# Sheet1.net
KiCad netlist of a schematic drawn in Altium Designer
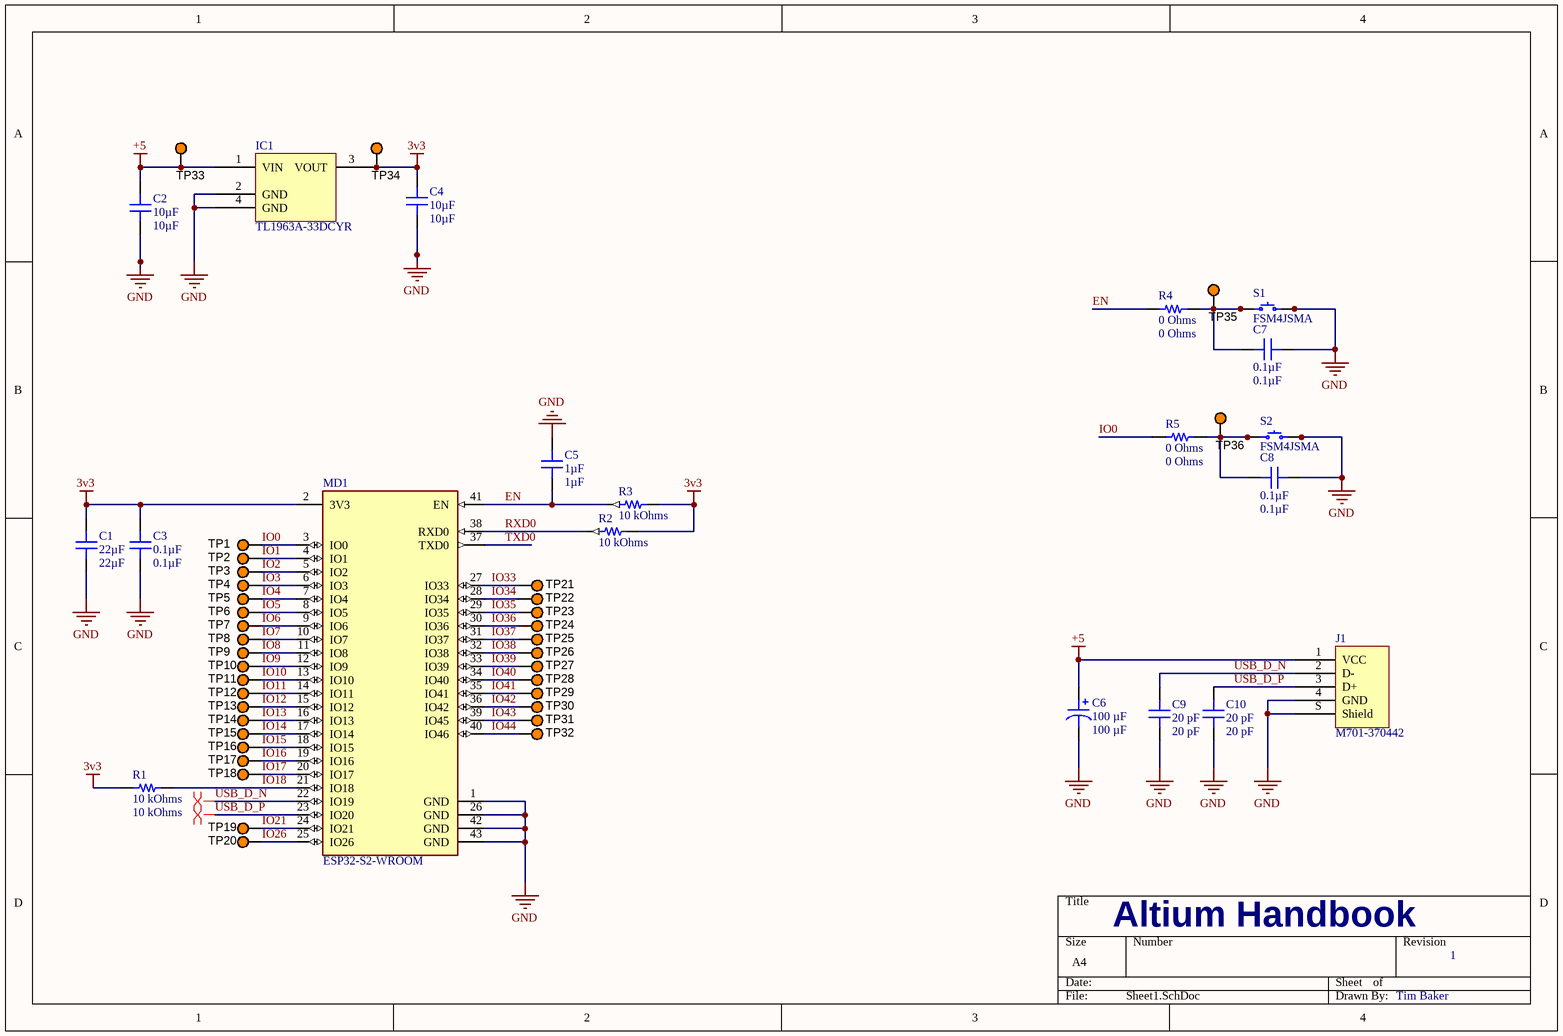
[diagram p0: Sheet1.SchDoc]

(export (version "E")
  (design (tool "Eeschema 10.0.6"))
  (components
    (comp (ref "C1")
      (value "22µF")
      (footprint "CAP 0805_2012")
      (description "CAP CER 22UF 10V X5R 0805")
      (fields (field (name "PART NUMBER") "0805ZD226MAT2A") (field (name "ALTIUM_VALUE") "22µF"))
      (libsource (lib "Celestial Altium Library - altium_library") (part "Capacitor"))
    )
    (comp (ref "C2")
      (value "10µF")
      (footprint "CAP 0805_2012")
      (description "CAP CER 10UF 10V X5R 0805")
      (fields (field (name "PART NUMBER") "0805ZD106KAT4A") (field (name "ALTIUM_VALUE") "10µF"))
      (libsource (lib "Celestial Altium Library - altium_library") (part "Capacitor"))
    )
    (comp (ref "C3")
      (value "0.1µF")
      (footprint "CAP 0805_2012")
      (description "CAP CER 0.1UF 10V X5R 0805")
      (fields (field (name "PART NUMBER") "0805ZD104KAT2A") (field (name "ALTIUM_VALUE") "0.1µF"))
      (libsource (lib "Celestial Altium Library - altium_library") (part "Capacitor"))
    )
    (comp (ref "C4")
      (value "10µF")
      (footprint "CAP 0805_2012")
      (description "CAP CER 10UF 10V X5R 0805")
      (fields (field (name "PART NUMBER") "0805ZD106KAT4A") (field (name "ALTIUM_VALUE") "10µF"))
      (libsource (lib "Celestial Altium Library - altium_library") (part "Capacitor"))
    )
    (comp (ref "C5")
      (value "1µF")
      (footprint "CAP 0805_2012")
      (description "CAP CER 1UF 10V X5R 0805")
      (fields (field (name "PART NUMBER") "0805ZD105KAT2A") (field (name "ALTIUM_VALUE") "1µF"))
      (libsource (lib "Celestial Altium Library - altium_library") (part "Capacitor"))
    )
    (comp (ref "C6")
      (value "100 µF")
      (footprint "CAP POL 2917_7343")
      (description "CAP TANT 100UF 10% 20V 2917")
      (fields (field (name "PART NUMBER") "T491X107K020AT") (field (name "ALTIUM_VALUE") "100 µF"))
      (libsource (lib "Celestial Altium Library - altium_library") (part "Polarised Capacitor"))
    )
    (comp (ref "C7")
      (value "0.1µF")
      (footprint "CAP 0805_2012")
      (description "CAP CER 0.1UF 10V X5R 0805")
      (fields (field (name "PART NUMBER") "0805ZD104KAT2A") (field (name "ALTIUM_VALUE") "0.1µF"))
      (libsource (lib "Celestial Altium Library - altium_library") (part "Capacitor"))
    )
    (comp (ref "C8")
      (value "0.1µF")
      (footprint "CAP 0805_2012")
      (description "CAP CER 0.1UF 10V X5R 0805")
      (fields (field (name "PART NUMBER") "0805ZD104KAT2A") (field (name "ALTIUM_VALUE") "0.1µF"))
      (libsource (lib "Celestial Altium Library - altium_library") (part "Capacitor"))
    )
    (comp (ref "C9")
      (value "20 pF")
      (footprint "CAP 0805_2012")
      (description "CAP CER 20PF 10V X8R 0805")
      (fields (field (name "PART NUMBER") "C0805C200G8HAC7800") (field (name "ALTIUM_VALUE") "20 pF"))
      (libsource (lib "Celestial Altium Library - altium_library") (part "Capacitor"))
    )
    (comp (ref "C10")
      (value "20 pF")
      (footprint "CAP 0805_2012")
      (description "CAP CER 20PF 10V X8R 0805")
      (fields (field (name "PART NUMBER") "C0805C200G8HAC7800") (field (name "ALTIUM_VALUE") "20 pF"))
      (libsource (lib "Celestial Altium Library - altium_library") (part "Capacitor"))
    )
    (comp (ref "IC1")
      (value "TL1963A-33DCYR")
      (footprint "TI SOT-223 DCY")
      (description "IC REG LINEAR 3.3V 1.5A SOT223-4")
      (libsource (lib "Celestial Altium Library - altium_library") (part "TI TL1963A DCY"))
    )
    (comp (ref "J1")
      (value "M701-370442")
      (footprint "HARWIN USB M701-370442")
      (description "CONN RCPT USB2.0 TYPEB 4P SMD RA")
      (libsource (lib "Celestial Altium Library - altium_library") (part "USB 2.0 Type B"))
    )
    (comp (ref "MD1")
      (value "ESP32-S2-WROOM")
      (footprint "FP-ESP32-S2-WROOM-MFG")
      (description "RX TXRX MOD WIFI SURFACE MOUNT")
      (libsource (lib "Altium Content Vault") (part "dfe856f8f0070eb901285bddcc8df6c"))
    )
    (comp (ref "R1")
      (value "10 kOhms")
      (footprint "RES 0805_2012")
      (description "RES 10K OHM 10% 1/8W 0805")
      (fields (field (name "PART NUMBER") "SG732ATTD103K") (field (name "ALTIUM_VALUE") "10 kOhms"))
      (libsource (lib "Celestial Altium Library - altium_library") (part "Resistor"))
    )
    (comp (ref "R2")
      (value "10 kOhms")
      (footprint "RES 0805_2012")
      (description "RES 10K OHM 10% 1/8W 0805")
      (fields (field (name "PART NUMBER") "SG732ATTD103K"))
      (libsource (lib "Celestial Altium Library - altium_library") (part "Resistor"))
    )
    (comp (ref "R3")
      (value "10 kOhms")
      (footprint "RES 0805_2012")
      (description "RES 10K OHM 10% 1/8W 0805")
      (fields (field (name "PART NUMBER") "SG732ATTD103K"))
      (libsource (lib "Celestial Altium Library - altium_library") (part "Resistor"))
    )
    (comp (ref "R4")
      (value "0 Ohms")
      (footprint "RES 0805_2012")
      (description "RES 0 OHM JUMPER 1/8W 0805")
      (fields (field (name "PART NUMBER") "CRCW08050000Z0EBC") (field (name "ALTIUM_VALUE") "0 Ohms"))
      (libsource (lib "") (part "Resistor_1"))
    )
    (comp (ref "R5")
      (value "0 Ohms")
      (footprint "RES 0805_2012")
      (description "RES 0 OHM JUMPER 1/8W 0805")
      (fields (field (name "PART NUMBER") "CRCW08050000Z0EBC") (field (name "ALTIUM_VALUE") "0 Ohms"))
      (libsource (lib "") (part "Resistor_1"))
    )
    (comp (ref "S1")
      (value "FSM4JSMA")
      (footprint "TE FSM4JSMA")
      (description "SWITCH TACTILE SPST-NO 0.05A 24V")
      (libsource (lib "Celestial Altium Library - altium_library") (part "SPST-NO 4 PIN"))
    )
    (comp (ref "S2")
      (value "FSM4JSMA")
      (footprint "TE FSM4JSMA")
      (description "SWITCH TACTILE SPST-NO 0.05A 24V")
      (libsource (lib "Celestial Altium Library - altium_library") (part "SPST-NO 4 PIN"))
    )
    (comp (ref "TP1")
      (value "Test Point Square")
      (footprint "New footprint 1")
      (description "1.5mm Square testpoint")
      (libsource (lib "Cuvos Pty Ltd") (part "TESTPOINT_ORANGE"))
    )
    (comp (ref "TP2")
      (value "Test Point Square")
      (footprint "New footprint 1")
      (description "1.5mm Square testpoint")
      (libsource (lib "Cuvos Pty Ltd") (part "TESTPOINT_ORANGE"))
    )
    (comp (ref "TP3")
      (value "Test Point Square")
      (footprint "New footprint 1")
      (description "1.5mm Square testpoint")
      (libsource (lib "Cuvos Pty Ltd") (part "TESTPOINT_ORANGE"))
    )
    (comp (ref "TP4")
      (value "Test Point Square")
      (footprint "New footprint 1")
      (description "1.5mm Square testpoint")
      (libsource (lib "Cuvos Pty Ltd") (part "TESTPOINT_ORANGE"))
    )
    (comp (ref "TP5")
      (value "Test Point Square")
      (footprint "New footprint 1")
      (description "1.5mm Square testpoint")
      (libsource (lib "Cuvos Pty Ltd") (part "TESTPOINT_ORANGE"))
    )
    (comp (ref "TP6")
      (value "Test Point Square")
      (footprint "New footprint 1")
      (description "1.5mm Square testpoint")
      (libsource (lib "Cuvos Pty Ltd") (part "TESTPOINT_ORANGE"))
    )
    (comp (ref "TP7")
      (value "Test Point Square")
      (footprint "New footprint 1")
      (description "1.5mm Square testpoint")
      (libsource (lib "Cuvos Pty Ltd") (part "TESTPOINT_ORANGE"))
    )
    (comp (ref "TP8")
      (value "Test Point Square")
      (footprint "New footprint 1")
      (description "1.5mm Square testpoint")
      (libsource (lib "Cuvos Pty Ltd") (part "TESTPOINT_ORANGE"))
    )
    (comp (ref "TP9")
      (value "Test Point Square")
      (footprint "New footprint 1")
      (description "1.5mm Square testpoint")
      (libsource (lib "Cuvos Pty Ltd") (part "TESTPOINT_ORANGE"))
    )
    (comp (ref "TP10")
      (value "Test Point Square")
      (footprint "New footprint 1")
      (description "1.5mm Square testpoint")
      (libsource (lib "Cuvos Pty Ltd") (part "TESTPOINT_ORANGE"))
    )
    (comp (ref "TP11")
      (value "Test Point Square")
      (footprint "New footprint 1")
      (description "1.5mm Square testpoint")
      (libsource (lib "Cuvos Pty Ltd") (part "TESTPOINT_ORANGE"))
    )
    (comp (ref "TP12")
      (value "Test Point Square")
      (footprint "New footprint 1")
      (description "1.5mm Square testpoint")
      (libsource (lib "Cuvos Pty Ltd") (part "TESTPOINT_ORANGE"))
    )
    (comp (ref "TP13")
      (value "Test Point Square")
      (footprint "New footprint 1")
      (description "1.5mm Square testpoint")
      (libsource (lib "Cuvos Pty Ltd") (part "TESTPOINT_ORANGE"))
    )
    (comp (ref "TP14")
      (value "Test Point Square")
      (footprint "New footprint 1")
      (description "1.5mm Square testpoint")
      (libsource (lib "Cuvos Pty Ltd") (part "TESTPOINT_ORANGE"))
    )
    (comp (ref "TP15")
      (value "Test Point Square")
      (footprint "New footprint 1")
      (description "1.5mm Square testpoint")
      (libsource (lib "Cuvos Pty Ltd") (part "TESTPOINT_ORANGE"))
    )
    (comp (ref "TP16")
      (value "Test Point Square")
      (footprint "New footprint 1")
      (description "1.5mm Square testpoint")
      (libsource (lib "Cuvos Pty Ltd") (part "TESTPOINT_ORANGE"))
    )
    (comp (ref "TP17")
      (value "Test Point Square")
      (footprint "New footprint 1")
      (description "1.5mm Square testpoint")
      (libsource (lib "Cuvos Pty Ltd") (part "TESTPOINT_ORANGE"))
    )
    (comp (ref "TP18")
      (value "Test Point Square")
      (footprint "New footprint 1")
      (description "1.5mm Square testpoint")
      (libsource (lib "Cuvos Pty Ltd") (part "TESTPOINT_ORANGE"))
    )
    (comp (ref "TP19")
      (value "Test Point Square")
      (footprint "New footprint 1")
      (description "1.5mm Square testpoint")
      (libsource (lib "Cuvos Pty Ltd") (part "TESTPOINT_ORANGE"))
    )
    (comp (ref "TP20")
      (value "Test Point Square")
      (footprint "New footprint 1")
      (description "1.5mm Square testpoint")
      (libsource (lib "Cuvos Pty Ltd") (part "TESTPOINT_ORANGE"))
    )
    (comp (ref "TP21")
      (value "Test Point Square")
      (footprint "New footprint 1")
      (description "1.5mm Square testpoint")
      (libsource (lib "Cuvos Pty Ltd") (part "TESTPOINT_ORANGE"))
    )
    (comp (ref "TP22")
      (value "Test Point Square")
      (footprint "New footprint 1")
      (description "1.5mm Square testpoint")
      (libsource (lib "Cuvos Pty Ltd") (part "TESTPOINT_ORANGE"))
    )
    (comp (ref "TP23")
      (value "Test Point Square")
      (footprint "New footprint 1")
      (description "1.5mm Square testpoint")
      (libsource (lib "Cuvos Pty Ltd") (part "TESTPOINT_ORANGE"))
    )
    (comp (ref "TP24")
      (value "Test Point Square")
      (footprint "New footprint 1")
      (description "1.5mm Square testpoint")
      (libsource (lib "Cuvos Pty Ltd") (part "TESTPOINT_ORANGE"))
    )
    (comp (ref "TP25")
      (value "Test Point Square")
      (footprint "New footprint 1")
      (description "1.5mm Square testpoint")
      (libsource (lib "Cuvos Pty Ltd") (part "TESTPOINT_ORANGE"))
    )
    (comp (ref "TP26")
      (value "Test Point Square")
      (footprint "New footprint 1")
      (description "1.5mm Square testpoint")
      (libsource (lib "Cuvos Pty Ltd") (part "TESTPOINT_ORANGE"))
    )
    (comp (ref "TP27")
      (value "Test Point Square")
      (footprint "New footprint 1")
      (description "1.5mm Square testpoint")
      (libsource (lib "Cuvos Pty Ltd") (part "TESTPOINT_ORANGE"))
    )
    (comp (ref "TP28")
      (value "Test Point Square")
      (footprint "New footprint 1")
      (description "1.5mm Square testpoint")
      (libsource (lib "Cuvos Pty Ltd") (part "TESTPOINT_ORANGE"))
    )
    (comp (ref "TP29")
      (value "Test Point Square")
      (footprint "New footprint 1")
      (description "1.5mm Square testpoint")
      (libsource (lib "Cuvos Pty Ltd") (part "TESTPOINT_ORANGE"))
    )
    (comp (ref "TP30")
      (value "Test Point Square")
      (footprint "New footprint 1")
      (description "1.5mm Square testpoint")
      (libsource (lib "Cuvos Pty Ltd") (part "TESTPOINT_ORANGE"))
    )
    (comp (ref "TP31")
      (value "Test Point Square")
      (footprint "New footprint 1")
      (description "1.5mm Square testpoint")
      (libsource (lib "Cuvos Pty Ltd") (part "TESTPOINT_ORANGE"))
    )
    (comp (ref "TP32")
      (value "Test Point Square")
      (footprint "New footprint 1")
      (description "1.5mm Square testpoint")
      (libsource (lib "Cuvos Pty Ltd") (part "TESTPOINT_ORANGE"))
    )
    (comp (ref "TP33")
      (value "Test Point Square")
      (footprint "New footprint 1")
      (description "1.5mm Square testpoint")
      (libsource (lib "Cuvos Pty Ltd") (part "TESTPOINT_ORANGE"))
    )
    (comp (ref "TP34")
      (value "Test Point Square")
      (footprint "New footprint 1")
      (description "1.5mm Square testpoint")
      (libsource (lib "Cuvos Pty Ltd") (part "TESTPOINT_ORANGE"))
    )
    (comp (ref "TP35")
      (value "Test Point Square")
      (footprint "New footprint 1")
      (description "1.5mm Square testpoint")
      (libsource (lib "Cuvos Pty Ltd") (part "TESTPOINT_ORANGE"))
    )
    (comp (ref "TP36")
      (value "Test Point Square")
      (footprint "New footprint 1")
      (description "1.5mm Square testpoint")
      (libsource (lib "Cuvos Pty Ltd") (part "TESTPOINT_ORANGE"))
    )
  )
  (nets
    (net (code "1") (name "+5") (class "Default")
      (node (ref "C2") (pin "2") (pinfunction "2_2") (pintype "passive"))
      (node (ref "C6") (pin "1") (pinfunction "1_1") (pintype "passive"))
      (node (ref "IC1") (pin "1") (pinfunction "VIN_1") (pintype "passive"))
      (node (ref "J1") (pin "1") (pinfunction "VCC_1") (pintype "passive"))
      (node (ref "TP33") (pin "1") (pinfunction "1_1") (pintype "passive"))
    )
    (net (code "2") (name "/EN") (class "Default")
      (node (ref "C5") (pin "1") (pinfunction "1_1") (pintype "passive"))
      (node (ref "MD1") (pin "41") (pinfunction "EN_41") (pintype "input"))
      (node (ref "R3") (pin "1") (pinfunction "1_1") (pintype "output"))
      (node (ref "R4") (pin "1") (pinfunction "1_1") (pintype "passive"))
    )
    (net (code "3") (name "/IO0") (class "Default")
      (node (ref "MD1") (pin "3") (pinfunction "IO0_3") (pintype "bidirectional"))
      (node (ref "R5") (pin "1") (pinfunction "1_1") (pintype "passive"))
      (node (ref "TP1") (pin "1") (pinfunction "1_1") (pintype "passive"))
    )
    (net (code "4") (name "/IO1") (class "Default")
      (node (ref "MD1") (pin "4") (pinfunction "IO1_4") (pintype "bidirectional"))
      (node (ref "TP2") (pin "1") (pinfunction "1_1") (pintype "passive"))
    )
    (net (code "5") (name "/IO2") (class "Default")
      (node (ref "MD1") (pin "5") (pinfunction "IO2_5") (pintype "bidirectional"))
      (node (ref "TP3") (pin "1") (pinfunction "1_1") (pintype "passive"))
    )
    (net (code "6") (name "/IO3") (class "Default")
      (node (ref "MD1") (pin "6") (pinfunction "IO3_6") (pintype "bidirectional"))
      (node (ref "TP4") (pin "1") (pinfunction "1_1") (pintype "passive"))
    )
    (net (code "7") (name "/IO4") (class "Default")
      (node (ref "MD1") (pin "7") (pinfunction "IO4_7") (pintype "bidirectional"))
      (node (ref "TP5") (pin "1") (pinfunction "1_1") (pintype "passive"))
    )
    (net (code "8") (name "/IO5") (class "Default")
      (node (ref "MD1") (pin "8") (pinfunction "IO5_8") (pintype "bidirectional"))
      (node (ref "TP6") (pin "1") (pinfunction "1_1") (pintype "passive"))
    )
    (net (code "9") (name "/IO6") (class "Default")
      (node (ref "MD1") (pin "9") (pinfunction "IO6_9") (pintype "bidirectional"))
      (node (ref "TP7") (pin "1") (pinfunction "1_1") (pintype "passive"))
    )
    (net (code "10") (name "/IO7") (class "Default")
      (node (ref "MD1") (pin "10") (pinfunction "IO7_10") (pintype "bidirectional"))
      (node (ref "TP8") (pin "1") (pinfunction "1_1") (pintype "passive"))
    )
    (net (code "11") (name "/IO8") (class "Default")
      (node (ref "MD1") (pin "11") (pinfunction "IO8_11") (pintype "bidirectional"))
      (node (ref "TP9") (pin "1") (pinfunction "1_1") (pintype "passive"))
    )
    (net (code "12") (name "/IO9") (class "Default")
      (node (ref "MD1") (pin "12") (pinfunction "IO9_12") (pintype "bidirectional"))
      (node (ref "TP10") (pin "1") (pinfunction "1_1") (pintype "passive"))
    )
    (net (code "13") (name "/IO10") (class "Default")
      (node (ref "MD1") (pin "13") (pinfunction "IO10_13") (pintype "bidirectional"))
      (node (ref "TP11") (pin "1") (pinfunction "1_1") (pintype "passive"))
    )
    (net (code "14") (name "/IO11") (class "Default")
      (node (ref "MD1") (pin "14") (pinfunction "IO11_14") (pintype "bidirectional"))
      (node (ref "TP12") (pin "1") (pinfunction "1_1") (pintype "passive"))
    )
    (net (code "15") (name "/IO12") (class "Default")
      (node (ref "MD1") (pin "15") (pinfunction "IO12_15") (pintype "bidirectional"))
      (node (ref "TP13") (pin "1") (pinfunction "1_1") (pintype "passive"))
    )
    (net (code "16") (name "/IO13") (class "Default")
      (node (ref "MD1") (pin "16") (pinfunction "IO13_16") (pintype "bidirectional"))
      (node (ref "TP14") (pin "1") (pinfunction "1_1") (pintype "passive"))
    )
    (net (code "17") (name "/IO14") (class "Default")
      (node (ref "MD1") (pin "17") (pinfunction "IO14_17") (pintype "bidirectional"))
      (node (ref "TP15") (pin "1") (pinfunction "1_1") (pintype "passive"))
    )
    (net (code "18") (name "/IO15") (class "Default")
      (node (ref "MD1") (pin "18") (pinfunction "IO15_18") (pintype "bidirectional"))
      (node (ref "TP16") (pin "1") (pinfunction "1_1") (pintype "passive"))
    )
    (net (code "19") (name "/IO16") (class "Default")
      (node (ref "MD1") (pin "19") (pinfunction "IO16_19") (pintype "bidirectional"))
      (node (ref "TP17") (pin "1") (pinfunction "1_1") (pintype "passive"))
    )
    (net (code "20") (name "/IO17") (class "Default")
      (node (ref "MD1") (pin "20") (pinfunction "IO17_20") (pintype "bidirectional"))
      (node (ref "TP18") (pin "1") (pinfunction "1_1") (pintype "passive"))
    )
    (net (code "21") (name "/IO18") (class "Default")
      (node (ref "MD1") (pin "21") (pinfunction "IO18_21") (pintype "bidirectional"))
      (node (ref "R1") (pin "2") (pinfunction "2_2") (pintype "passive"))
    )
    (net (code "22") (name "/IO21") (class "Default")
      (node (ref "MD1") (pin "24") (pinfunction "IO21_24") (pintype "bidirectional"))
      (node (ref "TP19") (pin "1") (pinfunction "1_1") (pintype "passive"))
    )
    (net (code "23") (name "/IO26") (class "Default")
      (node (ref "MD1") (pin "25") (pinfunction "IO26_25") (pintype "bidirectional"))
      (node (ref "TP20") (pin "1") (pinfunction "1_1") (pintype "passive"))
    )
    (net (code "24") (name "/IO33") (class "Default")
      (node (ref "MD1") (pin "27") (pinfunction "IO33_27") (pintype "bidirectional"))
      (node (ref "TP21") (pin "1") (pinfunction "1_1") (pintype "passive"))
    )
    (net (code "25") (name "/IO34") (class "Default")
      (node (ref "MD1") (pin "28") (pinfunction "IO34_28") (pintype "bidirectional"))
      (node (ref "TP22") (pin "1") (pinfunction "1_1") (pintype "passive"))
    )
    (net (code "26") (name "/IO35") (class "Default")
      (node (ref "MD1") (pin "29") (pinfunction "IO35_29") (pintype "bidirectional"))
      (node (ref "TP23") (pin "1") (pinfunction "1_1") (pintype "passive"))
    )
    (net (code "27") (name "/IO36") (class "Default")
      (node (ref "MD1") (pin "30") (pinfunction "IO36_30") (pintype "bidirectional"))
      (node (ref "TP24") (pin "1") (pinfunction "1_1") (pintype "passive"))
    )
    (net (code "28") (name "/IO37") (class "Default")
      (node (ref "MD1") (pin "31") (pinfunction "IO37_31") (pintype "bidirectional"))
      (node (ref "TP25") (pin "1") (pinfunction "1_1") (pintype "passive"))
    )
    (net (code "29") (name "/IO38") (class "Default")
      (node (ref "MD1") (pin "32") (pinfunction "IO38_32") (pintype "bidirectional"))
      (node (ref "TP26") (pin "1") (pinfunction "1_1") (pintype "passive"))
    )
    (net (code "30") (name "/IO39") (class "Default")
      (node (ref "MD1") (pin "33") (pinfunction "IO39_33") (pintype "bidirectional"))
      (node (ref "TP27") (pin "1") (pinfunction "1_1") (pintype "passive"))
    )
    (net (code "31") (name "/IO40") (class "Default")
      (node (ref "MD1") (pin "34") (pinfunction "IO40_34") (pintype "bidirectional"))
      (node (ref "TP28") (pin "1") (pinfunction "1_1") (pintype "passive"))
    )
    (net (code "32") (name "/IO41") (class "Default")
      (node (ref "MD1") (pin "35") (pinfunction "IO41_35") (pintype "bidirectional"))
      (node (ref "TP29") (pin "1") (pinfunction "1_1") (pintype "passive"))
    )
    (net (code "33") (name "/IO42") (class "Default")
      (node (ref "MD1") (pin "36") (pinfunction "IO42_36") (pintype "bidirectional"))
      (node (ref "TP30") (pin "1") (pinfunction "1_1") (pintype "passive"))
    )
    (net (code "34") (name "/IO43") (class "Default")
      (node (ref "MD1") (pin "39") (pinfunction "IO45_39") (pintype "bidirectional"))
      (node (ref "TP31") (pin "1") (pinfunction "1_1") (pintype "passive"))
    )
    (net (code "35") (name "/IO44") (class "Default")
      (node (ref "MD1") (pin "40") (pinfunction "IO46_40") (pintype "bidirectional"))
      (node (ref "TP32") (pin "1") (pinfunction "1_1") (pintype "passive"))
    )
    (net (code "36") (name "/RXD0") (class "Default")
      (node (ref "MD1") (pin "38") (pinfunction "RXD0_38") (pintype "input"))
      (node (ref "R2") (pin "1") (pinfunction "1_1") (pintype "output"))
    )
    (net (code "37") (name "/TXD0") (class "Default")
      (node (ref "MD1") (pin "37") (pinfunction "TXD0_37") (pintype "output"))
    )
    (net (code "38") (name "/USB_D_N") (class "Default")
      (node (ref "C9") (pin "1") (pinfunction "1_1") (pintype "passive"))
      (node (ref "J1") (pin "2") (pinfunction "D-_2") (pintype "passive"))
      (node (ref "MD1") (pin "22") (pinfunction "IO19_22") (pintype "bidirectional"))
    )
    (net (code "39") (name "/USB_D_P") (class "Default")
      (node (ref "C10") (pin "2") (pinfunction "2_2") (pintype "passive"))
      (node (ref "J1") (pin "3") (pinfunction "D+_3") (pintype "passive"))
      (node (ref "MD1") (pin "23") (pinfunction "IO20_23") (pintype "bidirectional"))
    )
    (net (code "40") (name "3v3") (class "Default")
      (node (ref "C1") (pin "1") (pinfunction "1_1") (pintype "passive"))
      (node (ref "C3") (pin "2") (pinfunction "2_2") (pintype "passive"))
      (node (ref "C4") (pin "1") (pinfunction "1_1") (pintype "passive"))
      (node (ref "IC1") (pin "3") (pinfunction "VOUT_3") (pintype "passive"))
      (node (ref "MD1") (pin "2") (pinfunction "3V3_2") (pintype "power_in"))
      (node (ref "R1") (pin "1") (pinfunction "1_1") (pintype "output"))
      (node (ref "R2") (pin "2") (pinfunction "2_2") (pintype "passive"))
      (node (ref "R3") (pin "2") (pinfunction "2_2") (pintype "passive"))
      (node (ref "TP34") (pin "1") (pinfunction "1_1") (pintype "passive"))
    )
    (net (code "41") (name "GND") (class "Default")
      (node (ref "C1") (pin "2") (pinfunction "2_2") (pintype "passive"))
      (node (ref "C10") (pin "1") (pinfunction "1_1") (pintype "passive"))
      (node (ref "C2") (pin "1") (pinfunction "1_1") (pintype "passive"))
      (node (ref "C3") (pin "1") (pinfunction "1_1") (pintype "passive"))
      (node (ref "C4") (pin "2") (pinfunction "2_2") (pintype "passive"))
      (node (ref "C5") (pin "2") (pinfunction "2_2") (pintype "passive"))
      (node (ref "C6") (pin "2") (pinfunction "2_2") (pintype "passive"))
      (node (ref "C7") (pin "1") (pinfunction "1_1") (pintype "passive"))
      (node (ref "C8") (pin "1") (pinfunction "1_1") (pintype "passive"))
      (node (ref "C9") (pin "2") (pinfunction "2_2") (pintype "passive"))
      (node (ref "IC1") (pin "2") (pinfunction "GND_2") (pintype "passive"))
      (node (ref "IC1") (pin "4") (pinfunction "GND_4") (pintype "passive"))
      (node (ref "J1") (pin "4") (pinfunction "GND_4") (pintype "passive"))
      (node (ref "J1") (pin "S") (pinfunction "Shield_S") (pintype "passive"))
      (node (ref "MD1") (pin "1") (pinfunction "GND_1") (pintype "power_in"))
      (node (ref "MD1") (pin "26") (pinfunction "GND_26") (pintype "power_in"))
      (node (ref "MD1") (pin "42") (pinfunction "GND_42") (pintype "power_in"))
      (node (ref "MD1") (pin "43") (pinfunction "GND_43") (pintype "power_in"))
      (node (ref "S1") (pin "3") (pinfunction "3_3") (pintype "passive"))
      (node (ref "S1") (pin "4") (pinfunction "4_4") (pintype "passive"))
      (node (ref "S2") (pin "3") (pinfunction "3_3") (pintype "passive"))
      (node (ref "S2") (pin "4") (pinfunction "4_4") (pintype "passive"))
    )
    (net (code "42") (name "Net-(C7-Pad2)") (class "Default")
      (node (ref "C7") (pin "2") (pinfunction "2_2") (pintype "passive"))
      (node (ref "R4") (pin "2") (pinfunction "2_2") (pintype "passive"))
      (node (ref "S1") (pin "1") (pinfunction "1_1") (pintype "passive"))
      (node (ref "S1") (pin "2") (pinfunction "2_2") (pintype "passive"))
      (node (ref "TP35") (pin "1") (pinfunction "1_1") (pintype "passive"))
    )
    (net (code "43") (name "Net-(C8-Pad2)") (class "Default")
      (node (ref "C8") (pin "2") (pinfunction "2_2") (pintype "passive"))
      (node (ref "R5") (pin "2") (pinfunction "2_2") (pintype "passive"))
      (node (ref "S2") (pin "1") (pinfunction "1_1") (pintype "passive"))
      (node (ref "S2") (pin "2") (pinfunction "2_2") (pintype "passive"))
      (node (ref "TP36") (pin "1") (pinfunction "1_1") (pintype "passive"))
    )
  )
)
